# V-00349-01.net
KiCad netlist of a schematic drawn in EAGLE
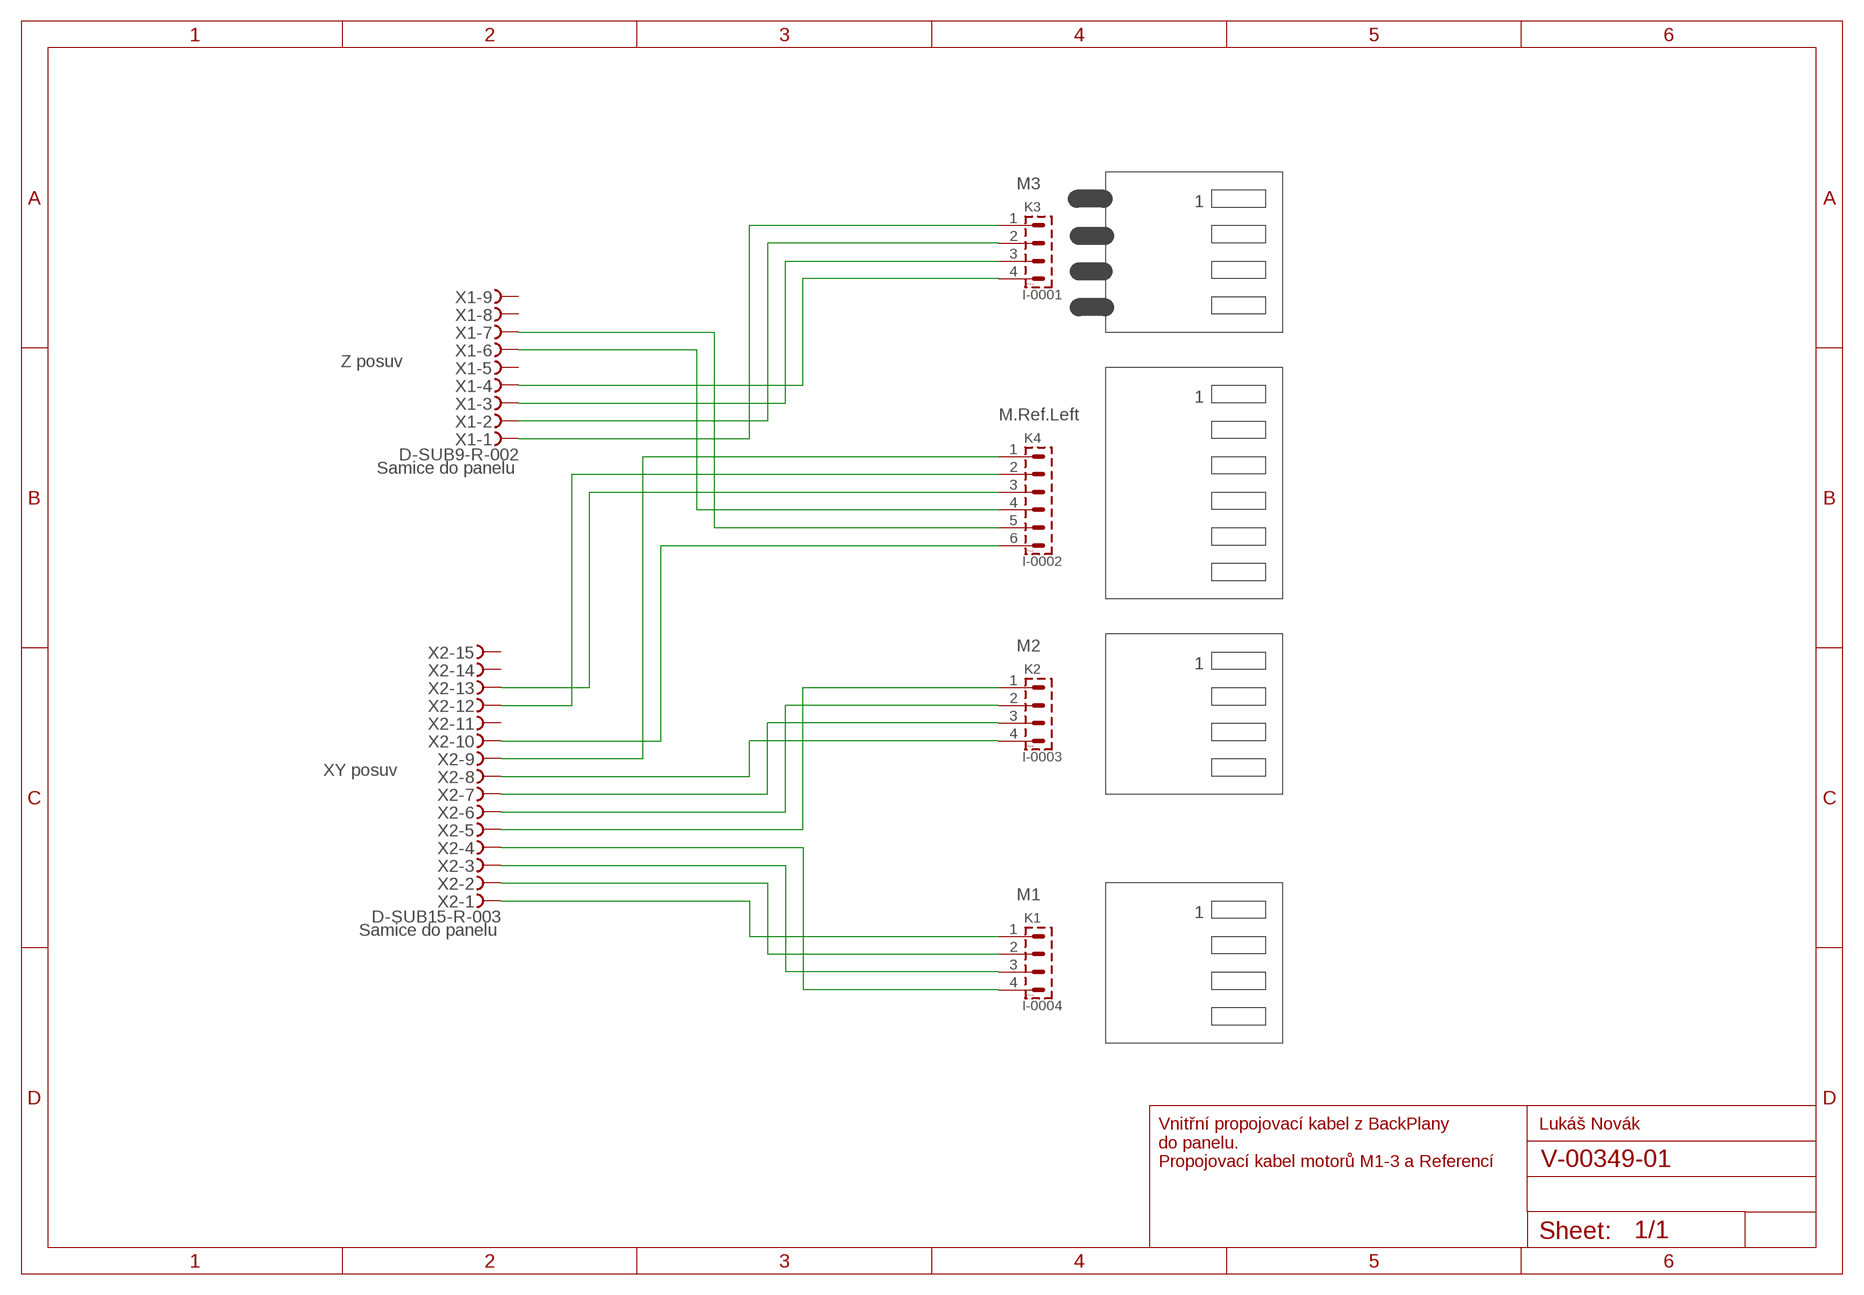
[diagram p0: schematic, sheet 1]

(export (version "E")
  (design (tool "Eeschema 10.0.6"))
  (components
    (comp (ref "K1")
      (value "I-0004")
      (footprint "eagle-import:PSH02-04P")
      (libsource (lib "eagle-import") (part "PSH02-04P"))
    )
    (comp (ref "K2")
      (value "I-0003")
      (footprint "eagle-import:PSH02-04P")
      (libsource (lib "eagle-import") (part "PSH02-04P"))
    )
    (comp (ref "K3")
      (value "I-0001")
      (footprint "eagle-import:PSH02-04P")
      (libsource (lib "eagle-import") (part "PSH02-04P"))
    )
    (comp (ref "K4")
      (value "I-0002")
      (footprint "eagle-import:PSH02-06P")
      (libsource (lib "eagle-import") (part "PSH02-06P"))
    )
    (comp (ref "X1")
      (value "D-SUB9-R-002")
      (footprint "eagle-import:H2M09ST")
      (libsource (lib "eagle-import") (part "D-SUB9-H2M09ST"))
    )
    (comp (ref "X2")
      (value "D-SUB15-R-003")
      (footprint "eagle-import:H2M15ST")
      (libsource (lib "eagle-import") (part "D-SUB15-H2M15ST"))
    )
  )
  (nets
    (net (code "1") (name "Net-(X1A-F)") (class "Default")
      (node (ref "K3") (pin "1") (pinfunction "1_1") (pintype "passive"))
      (node (ref "X1") (pin "1") (pinfunction "F_1") (pintype "passive"))
    )
    (net (code "2") (name "Net-(X1B-F)") (class "Default")
      (node (ref "K3") (pin "2") (pinfunction "2_2") (pintype "passive"))
      (node (ref "X1") (pin "2") (pinfunction "F_2") (pintype "passive"))
    )
    (net (code "3") (name "Net-(X1C-F)") (class "Default")
      (node (ref "K3") (pin "3") (pinfunction "3_3") (pintype "passive"))
      (node (ref "X1") (pin "3") (pinfunction "F_3") (pintype "passive"))
    )
    (net (code "4") (name "Net-(X1D-F)") (class "Default")
      (node (ref "K3") (pin "4") (pinfunction "4_4") (pintype "passive"))
      (node (ref "X1") (pin "4") (pinfunction "F_4") (pintype "passive"))
    )
    (net (code "5") (name "Net-(X1F-F)") (class "Default")
      (node (ref "K4") (pin "4") (pinfunction "4_4") (pintype "passive"))
      (node (ref "X1") (pin "6") (pinfunction "F_6") (pintype "passive"))
    )
    (net (code "6") (name "Net-(X1G-F)") (class "Default")
      (node (ref "K4") (pin "5") (pinfunction "5_5") (pintype "passive"))
      (node (ref "X1") (pin "7") (pinfunction "F_7") (pintype "passive"))
    )
    (net (code "7") (name "Net-(X2A-F)") (class "Default")
      (node (ref "K1") (pin "1") (pinfunction "1_1") (pintype "passive"))
      (node (ref "X2") (pin "1") (pinfunction "F_1") (pintype "passive"))
    )
    (net (code "8") (name "Net-(X2B-F)") (class "Default")
      (node (ref "K4") (pin "6") (pinfunction "6_6") (pintype "passive"))
      (node (ref "X2") (pin "10") (pinfunction "F_10") (pintype "passive"))
    )
    (net (code "9") (name "Net-(X2D-F)") (class "Default")
      (node (ref "K4") (pin "2") (pinfunction "2_2") (pintype "passive"))
      (node (ref "X2") (pin "12") (pinfunction "F_12") (pintype "passive"))
    )
    (net (code "10") (name "Net-(X2E-F)") (class "Default")
      (node (ref "K4") (pin "3") (pinfunction "3_3") (pintype "passive"))
      (node (ref "X2") (pin "13") (pinfunction "F_13") (pintype "passive"))
    )
    (net (code "11") (name "Net-(X2H-F)") (class "Default")
      (node (ref "K1") (pin "2") (pinfunction "2_2") (pintype "passive"))
      (node (ref "X2") (pin "2") (pinfunction "F_2") (pintype "passive"))
    )
    (net (code "12") (name "Net-(X2I-F)") (class "Default")
      (node (ref "K1") (pin "3") (pinfunction "3_3") (pintype "passive"))
      (node (ref "X2") (pin "3") (pinfunction "F_3") (pintype "passive"))
    )
    (net (code "13") (name "Net-(X2J-F)") (class "Default")
      (node (ref "K1") (pin "4") (pinfunction "4_4") (pintype "passive"))
      (node (ref "X2") (pin "4") (pinfunction "F_4") (pintype "passive"))
    )
    (net (code "14") (name "Net-(X2K-F)") (class "Default")
      (node (ref "K2") (pin "1") (pinfunction "1_1") (pintype "passive"))
      (node (ref "X2") (pin "5") (pinfunction "F_5") (pintype "passive"))
    )
    (net (code "15") (name "Net-(X2L-F)") (class "Default")
      (node (ref "K2") (pin "2") (pinfunction "2_2") (pintype "passive"))
      (node (ref "X2") (pin "6") (pinfunction "F_6") (pintype "passive"))
    )
    (net (code "16") (name "Net-(X2M-F)") (class "Default")
      (node (ref "K2") (pin "3") (pinfunction "3_3") (pintype "passive"))
      (node (ref "X2") (pin "7") (pinfunction "F_7") (pintype "passive"))
    )
    (net (code "17") (name "Net-(X2N-F)") (class "Default")
      (node (ref "K2") (pin "4") (pinfunction "4_4") (pintype "passive"))
      (node (ref "X2") (pin "8") (pinfunction "F_8") (pintype "passive"))
    )
    (net (code "18") (name "Net-(X2O-F)") (class "Default")
      (node (ref "K4") (pin "1") (pinfunction "1_1") (pintype "passive"))
      (node (ref "X2") (pin "9") (pinfunction "F_9") (pintype "passive"))
    )
    (net (code "19") (name "unconnected-(X1E-F-Pad5)") (class "Default")
      (node (ref "X1") (pin "5") (pinfunction "F_5") (pintype "passive"))
    )
    (net (code "20") (name "unconnected-(X1H-F-Pad8)") (class "Default")
      (node (ref "X1") (pin "8") (pinfunction "F_8") (pintype "passive"))
    )
    (net (code "21") (name "unconnected-(X1I-F-Pad9)") (class "Default")
      (node (ref "X1") (pin "9") (pinfunction "F_9") (pintype "passive"))
    )
    (net (code "22") (name "unconnected-(X2C-F-Pad11)") (class "Default")
      (node (ref "X2") (pin "11") (pinfunction "F_11") (pintype "passive"))
    )
    (net (code "23") (name "unconnected-(X2F-F-Pad14)") (class "Default")
      (node (ref "X2") (pin "14") (pinfunction "F_14") (pintype "passive"))
    )
    (net (code "24") (name "unconnected-(X2G-F-Pad15)") (class "Default")
      (node (ref "X2") (pin "15") (pinfunction "F_15") (pintype "passive"))
    )
  )
)
